# 6coils-1-discrete.net
KiCad netlist of a schematic drawn in EasyEDA
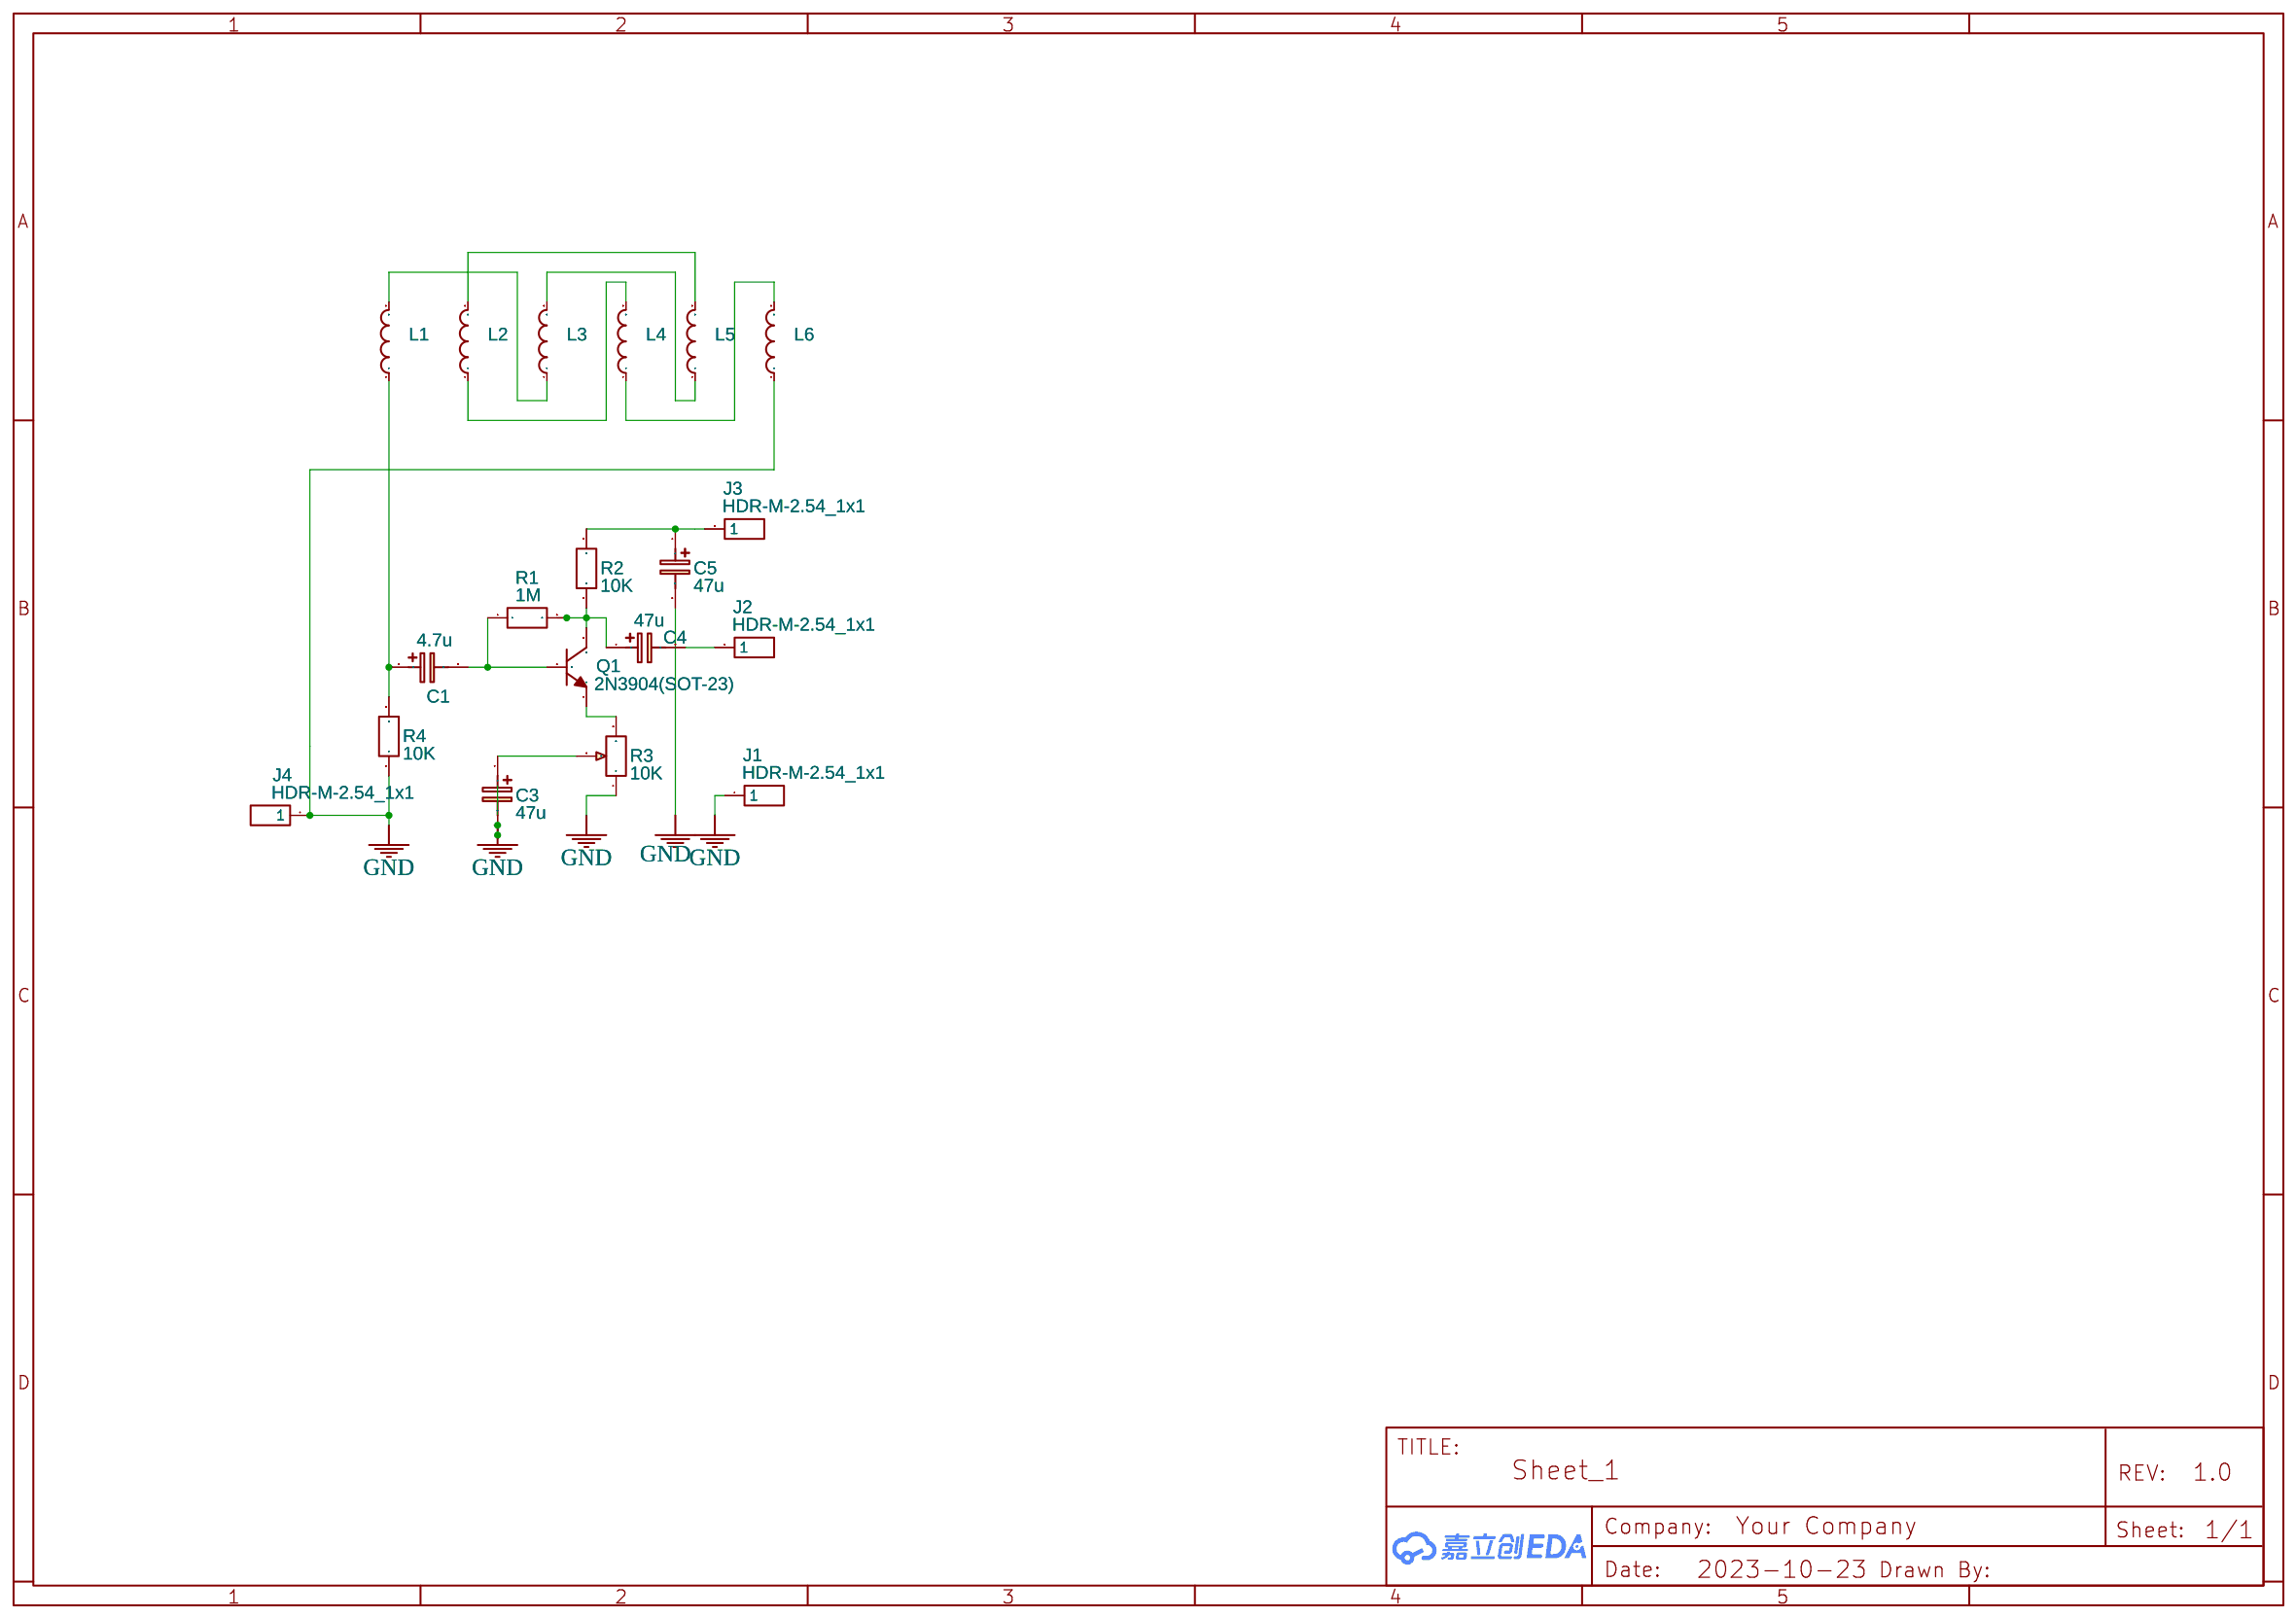
[diagram p0: schematic sheet]

(export (version "E")
  (design (tool "Eeschema 10.0.6"))
  (components
    (comp (ref "C1") (value "4.7u") (libsource (lib "") (part "C_Tan_SMD_A_EU")))
    (comp (ref "C3") (value "47u") (libsource (lib "") (part "C_Tan_SMD_A_EU_3")))
    (comp (ref "C4") (value "47u") (libsource (lib "") (part "C_Tan_SMD_A_EU_1")))
    (comp (ref "C5") (value "47u") (libsource (lib "") (part "C_Tan_SMD_A_EU_2")))
    (comp (ref "J1")
      (value "HDR-M-2.54_1x1")
      (fields (field (name "BOM_Supplier Part") "C81276"))
      (libsource (lib "") (part "HDR-M-2.54_1x1"))
    )
    (comp (ref "J2")
      (value "HDR-M-2.54_1x1")
      (fields (field (name "BOM_Supplier Part") "C81276"))
      (libsource (lib "") (part "HDR-M-2.54_1x1"))
    )
    (comp (ref "J3")
      (value "HDR-M-2.54_1x1")
      (fields (field (name "BOM_Supplier Part") "C81276"))
      (libsource (lib "") (part "HDR-M-2.54_1x1"))
    )
    (comp (ref "J4")
      (value "HDR-M-2.54_1x1")
      (fields (field (name "BOM_Supplier Part") "C81276"))
      (libsource (lib "") (part "HDR-M-2.54_1x1_1"))
    )
    (comp (ref "L1")
      (value "INDUCTOR_SMD:L_COILCRAFT_XXL4040")
      (fields (field (name "Manufacturer Part") "Inductor_SMD:L_Coilcraft_XxL4040"))
      (libsource (lib "") (part "INDUCTOR_SMD{colon}L_COILCRAFT_XXL4040_1"))
    )
    (comp (ref "L2")
      (value "INDUCTOR_SMD:L_COILCRAFT_XXL4040")
      (fields (field (name "Manufacturer Part") "Inductor_SMD:L_Coilcraft_XxL4040"))
      (libsource (lib "") (part "INDUCTOR_SMD{colon}L_COILCRAFT_XXL4040_1"))
    )
    (comp (ref "L3")
      (value "INDUCTOR_SMD:L_COILCRAFT_XXL4040")
      (fields (field (name "Manufacturer Part") "Inductor_SMD:L_Coilcraft_XxL4040"))
      (libsource (lib "") (part "INDUCTOR_SMD{colon}L_COILCRAFT_XXL4040"))
    )
    (comp (ref "L4")
      (value "INDUCTOR_SMD:L_COILCRAFT_XXL4040")
      (fields (field (name "Manufacturer Part") "Inductor_SMD:L_Coilcraft_XxL4040"))
      (libsource (lib "") (part "INDUCTOR_SMD{colon}L_COILCRAFT_XXL4040"))
    )
    (comp (ref "L5")
      (value "INDUCTOR_SMD:L_COILCRAFT_XXL4040")
      (fields (field (name "Manufacturer Part") "Inductor_SMD:L_Coilcraft_XxL4040"))
      (libsource (lib "") (part "INDUCTOR_SMD{colon}L_COILCRAFT_XXL4040"))
    )
    (comp (ref "L6")
      (value "INDUCTOR_SMD:L_COILCRAFT_XXL4040")
      (fields (field (name "Manufacturer Part") "Inductor_SMD:L_Coilcraft_XxL4040"))
      (libsource (lib "") (part "INDUCTOR_SMD{colon}L_COILCRAFT_XXL4040"))
    )
    (comp (ref "Q1")
      (value "2N3904(SOT-23)")
      (fields
        (field (name "BOM_Manufacturer Part") "2n3904S-RTK/PS")
        (field (name "BOM_Supplier Part") "C18536")
      )
      (libsource (lib "") (part "2N3904(SOT-23)"))
    )
    (comp (ref "R1") (value "1M") (libsource (lib "") (part "R_0603_EU_1")))
    (comp (ref "R2") (value "10K") (libsource (lib "") (part "R_0603_EU")))
    (comp (ref "R3")
      (value "10K")
      (fields (field (name "Manufacturer Part") "RM063-103 10K") (field (name "Manufacturer") "JML"))
      (libsource (lib "") (part "RM063-103 10K"))
    )
    (comp (ref "R4") (value "10K") (libsource (lib "") (part "R_0603_EU")))
  )
  (nets
    (net (code "1") (name "GND") (class "Default")
      (node (ref "C3") (pin "2") (pinfunction "2_2") (pintype "unspecified"))
      (node (ref "C5") (pin "2") (pinfunction "2_2") (pintype "unspecified"))
      (node (ref "J1") (pin "1") (pinfunction "1_1") (pintype "input"))
      (node (ref "J4") (pin "1") (pinfunction "1_1") (pintype "input"))
      (node (ref "L6") (pin "1") (pinfunction "1_1") (pintype "unspecified"))
      (node (ref "R3") (pin "1") (pinfunction "1_1") (pintype "input"))
      (node (ref "R4") (pin "1") (pinfunction "1_1") (pintype "unspecified"))
    )
    (net (code "2") (name "Net-(C1-Pad1)") (class "Default")
      (node (ref "C1") (pin "1") (pinfunction "1_1") (pintype "unspecified"))
      (node (ref "L1") (pin "1") (pinfunction "1_1") (pintype "unspecified"))
      (node (ref "R4") (pin "2") (pinfunction "2_2") (pintype "unspecified"))
    )
    (net (code "3") (name "Net-(C3-Pad1)") (class "Default")
      (node (ref "C3") (pin "1") (pinfunction "1_1") (pintype "unspecified"))
      (node (ref "R3") (pin "2") (pinfunction "2_2") (pintype "input"))
    )
    (net (code "4") (name "Net-(C4-Pad2)") (class "Default")
      (node (ref "C4") (pin "2") (pinfunction "2_2") (pintype "unspecified"))
      (node (ref "J2") (pin "1") (pinfunction "1_1") (pintype "input"))
    )
    (net (code "5") (name "Net-(C5-Pad1)") (class "Default")
      (node (ref "C5") (pin "1") (pinfunction "1_1") (pintype "unspecified"))
      (node (ref "J3") (pin "1") (pinfunction "1_1") (pintype "input"))
      (node (ref "R2") (pin "2") (pinfunction "2_2") (pintype "unspecified"))
    )
    (net (code "6") (name "Net-(L1-Pad2)") (class "Default")
      (node (ref "L1") (pin "2") (pinfunction "2_2") (pintype "unspecified"))
      (node (ref "L3") (pin "1") (pinfunction "1_1") (pintype "unspecified"))
    )
    (net (code "7") (name "Net-(L2-Pad1)") (class "Default")
      (node (ref "L2") (pin "1") (pinfunction "1_1") (pintype "unspecified"))
      (node (ref "L4") (pin "2") (pinfunction "2_2") (pintype "unspecified"))
    )
    (net (code "8") (name "Net-(L2-Pad2)") (class "Default")
      (node (ref "L2") (pin "2") (pinfunction "2_2") (pintype "unspecified"))
      (node (ref "L5") (pin "2") (pinfunction "2_2") (pintype "unspecified"))
    )
    (net (code "9") (name "Net-(L3-Pad2)") (class "Default")
      (node (ref "L3") (pin "2") (pinfunction "2_2") (pintype "unspecified"))
      (node (ref "L5") (pin "1") (pinfunction "1_1") (pintype "unspecified"))
    )
    (net (code "10") (name "Net-(L4-Pad1)") (class "Default")
      (node (ref "L4") (pin "1") (pinfunction "1_1") (pintype "unspecified"))
      (node (ref "L6") (pin "2") (pinfunction "2_2") (pintype "unspecified"))
    )
    (net (code "11") (name "Net-(Q1-B)") (class "Default")
      (node (ref "C1") (pin "2") (pinfunction "2_2") (pintype "unspecified"))
      (node (ref "Q1") (pin "2") (pinfunction "B_2") (pintype "input"))
      (node (ref "R1") (pin "1") (pinfunction "1_1") (pintype "unspecified"))
    )
    (net (code "12") (name "Net-(Q1-C)") (class "Default")
      (node (ref "C4") (pin "1") (pinfunction "1_1") (pintype "unspecified"))
      (node (ref "Q1") (pin "3") (pinfunction "C_3") (pintype "input"))
      (node (ref "R1") (pin "2") (pinfunction "2_2") (pintype "unspecified"))
      (node (ref "R2") (pin "1") (pinfunction "1_1") (pintype "unspecified"))
    )
    (net (code "13") (name "Net-(Q1-E)") (class "Default")
      (node (ref "Q1") (pin "1") (pinfunction "E_1") (pintype "input"))
      (node (ref "R3") (pin "3") (pinfunction "3_3") (pintype "input"))
    )
  )
)
